# InsideLift.net
KiCad netlist of a schematic drawn in EAGLE
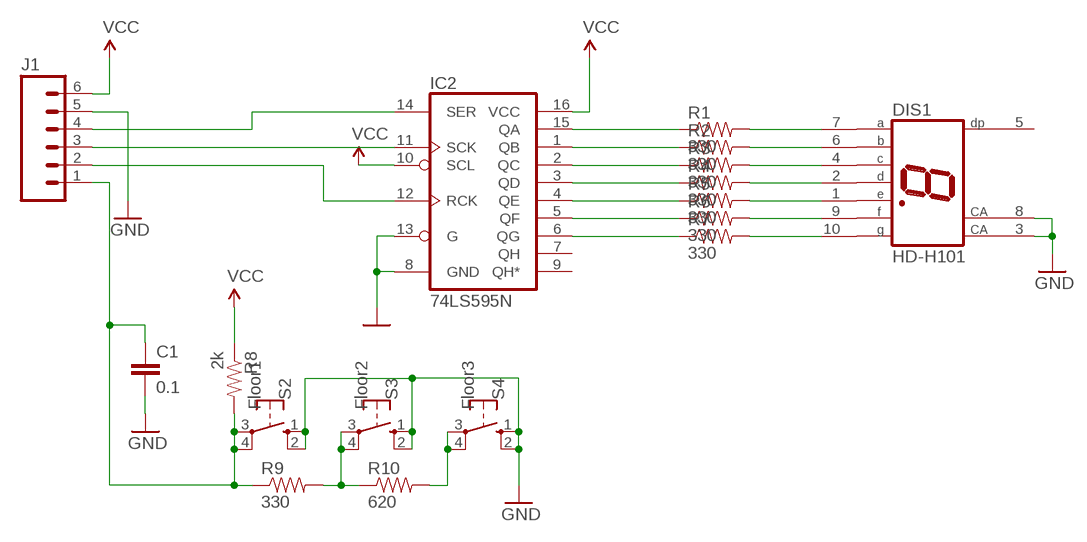
[diagram p0: schematic, sheet 1]

(export (version "E")
  (design (tool "Eeschema 10.0.6"))
  (components
    (comp (ref "C1")
      (value "0.1")
      (footprint "eagle-import:CAP-PTH-5MM")
      (libsource (lib "eagle-import") (part "CAPPTH1"))
    )
    (comp (ref "DIS1")
      (value "HD-H101")
      (footprint "eagle-import:HDSP-M")
      (libsource (lib "eagle-import") (part "HD-H101"))
    )
    (comp (ref "IC2")
      (value "74LS595N")
      (footprint "eagle-import:DIL16")
      (libsource (lib "eagle-import") (part "74595NLS"))
    )
    (comp (ref "J1")
      (value "M06LONGPADS")
      (footprint "eagle-import:1X06_LONGPADS")
      (libsource (lib "eagle-import") (part "M06LONGPADS"))
    )
    (comp (ref "R1")
      (value "330")
      (footprint "eagle-import:AXIAL-0.3")
      (libsource (lib "eagle-import") (part "SparkFun-Resistors_RESISTORAXIAL-0.3"))
    )
    (comp (ref "R2")
      (value "330")
      (footprint "eagle-import:AXIAL-0.3")
      (libsource (lib "eagle-import") (part "SparkFun-Resistors_RESISTORAXIAL-0.3"))
    )
    (comp (ref "R3")
      (value "330")
      (footprint "eagle-import:AXIAL-0.3")
      (libsource (lib "eagle-import") (part "SparkFun-Resistors_RESISTORAXIAL-0.3"))
    )
    (comp (ref "R4")
      (value "330")
      (footprint "eagle-import:AXIAL-0.3")
      (libsource (lib "eagle-import") (part "SparkFun-Resistors_RESISTORAXIAL-0.3"))
    )
    (comp (ref "R5")
      (value "330")
      (footprint "eagle-import:AXIAL-0.3")
      (libsource (lib "eagle-import") (part "SparkFun-Resistors_RESISTORAXIAL-0.3"))
    )
    (comp (ref "R6")
      (value "330")
      (footprint "eagle-import:AXIAL-0.3")
      (libsource (lib "eagle-import") (part "SparkFun-Resistors_RESISTORAXIAL-0.3"))
    )
    (comp (ref "R7")
      (value "330")
      (footprint "eagle-import:AXIAL-0.3")
      (libsource (lib "eagle-import") (part "SparkFun-Resistors_RESISTORAXIAL-0.3"))
    )
    (comp (ref "R8")
      (value "2k")
      (footprint "eagle-import:0805")
      (libsource (lib "eagle-import") (part "RESISTOR0805-RES"))
    )
    (comp (ref "R9")
      (value "330")
      (footprint "eagle-import:0805")
      (libsource (lib "eagle-import") (part "RESISTOR0805-RES"))
    )
    (comp (ref "R10")
      (value "620")
      (footprint "eagle-import:0805")
      (libsource (lib "eagle-import") (part "RESISTOR0805-RES"))
    )
    (comp (ref "S2")
      (value "Floor1")
      (footprint "eagle-import:B3F-10XX")
      (fields
        (field (name "MPN") "B3F-1000")
        (field (name "MPN_1") "B3F-1000")
        (field (name "OC_FARNELL") "176432")
        (field (name "OC_NEWARK") "36M3542")
      )
      (libsource (lib "eagle-import") (part "10-XX"))
    )
    (comp (ref "S3")
      (value "Floor2")
      (footprint "eagle-import:B3F-10XX")
      (fields
        (field (name "MPN") "B3F-1000")
        (field (name "MPN_1") "B3F-1000")
        (field (name "OC_FARNELL") "176432")
        (field (name "OC_NEWARK") "36M3542")
      )
      (libsource (lib "eagle-import") (part "10-XX"))
    )
    (comp (ref "S4")
      (value "Floor3")
      (footprint "eagle-import:B3F-10XX")
      (fields
        (field (name "MPN") "B3F-1000")
        (field (name "MPN_1") "B3F-1000")
        (field (name "OC_FARNELL") "176432")
        (field (name "OC_NEWARK") "36M3542")
      )
      (libsource (lib "eagle-import") (part "10-XX"))
    )
  )
  (nets
    (net (code "1") (name "GND") (class "Default")
      (node (ref "C1") (pin "2") (pinfunction "2_2") (pintype "passive"))
      (node (ref "DIS1") (pin "3") (pinfunction "CA_3") (pintype "passive"))
      (node (ref "DIS1") (pin "8") (pinfunction "CA_8") (pintype "passive"))
      (node (ref "IC2") (pin "13") (pinfunction "G_13") (pintype "input"))
      (node (ref "IC2") (pin "8") (pinfunction "GND_8") (pintype "power_in"))
      (node (ref "J1") (pin "5") (pinfunction "5_5") (pintype "passive"))
      (node (ref "S2") (pin "1") (pinfunction "S_1") (pintype "passive"))
      (node (ref "S2") (pin "2") (pinfunction "S1_2") (pintype "passive"))
      (node (ref "S3") (pin "1") (pinfunction "S_1") (pintype "passive"))
      (node (ref "S3") (pin "2") (pinfunction "S1_2") (pintype "passive"))
      (node (ref "S4") (pin "1") (pinfunction "S_1") (pintype "passive"))
      (node (ref "S4") (pin "2") (pinfunction "S1_2") (pintype "passive"))
    )
    (net (code "2") (name "Net-(DIS1-A)") (class "Default")
      (node (ref "DIS1") (pin "7") (pinfunction "A_7") (pintype "passive"))
      (node (ref "R1") (pin "P$2") (pinfunction "2_P$2") (pintype "passive"))
    )
    (net (code "3") (name "Net-(DIS1-B)") (class "Default")
      (node (ref "DIS1") (pin "6") (pinfunction "B_6") (pintype "passive"))
      (node (ref "R2") (pin "P$2") (pinfunction "2_P$2") (pintype "passive"))
    )
    (net (code "4") (name "Net-(DIS1-C)") (class "Default")
      (node (ref "DIS1") (pin "4") (pinfunction "C_4") (pintype "passive"))
      (node (ref "R3") (pin "P$2") (pinfunction "2_P$2") (pintype "passive"))
    )
    (net (code "5") (name "Net-(DIS1-D)") (class "Default")
      (node (ref "DIS1") (pin "2") (pinfunction "D_2") (pintype "passive"))
      (node (ref "R4") (pin "P$2") (pinfunction "2_P$2") (pintype "passive"))
    )
    (net (code "6") (name "Net-(DIS1-E)") (class "Default")
      (node (ref "DIS1") (pin "1") (pinfunction "E_1") (pintype "passive"))
      (node (ref "R5") (pin "P$2") (pinfunction "2_P$2") (pintype "passive"))
    )
    (net (code "7") (name "Net-(DIS1-F)") (class "Default")
      (node (ref "DIS1") (pin "9") (pinfunction "F_9") (pintype "passive"))
      (node (ref "R6") (pin "P$2") (pinfunction "2_P$2") (pintype "passive"))
    )
    (net (code "8") (name "Net-(DIS1-G)") (class "Default")
      (node (ref "DIS1") (pin "10") (pinfunction "G_10") (pintype "passive"))
      (node (ref "R7") (pin "P$2") (pinfunction "2_P$2") (pintype "passive"))
    )
    (net (code "9") (name "Net-(IC2-QA)") (class "Default")
      (node (ref "IC2") (pin "15") (pinfunction "QA_15") (pintype "tri_state"))
      (node (ref "R1") (pin "P$1") (pinfunction "1_P$1") (pintype "passive"))
    )
    (net (code "10") (name "Net-(IC2-QB)") (class "Default")
      (node (ref "IC2") (pin "1") (pinfunction "QB_1") (pintype "tri_state"))
      (node (ref "R2") (pin "P$1") (pinfunction "1_P$1") (pintype "passive"))
    )
    (net (code "11") (name "Net-(IC2-QC)") (class "Default")
      (node (ref "IC2") (pin "2") (pinfunction "QC_2") (pintype "tri_state"))
      (node (ref "R3") (pin "P$1") (pinfunction "1_P$1") (pintype "passive"))
    )
    (net (code "12") (name "Net-(IC2-QD)") (class "Default")
      (node (ref "IC2") (pin "3") (pinfunction "QD_3") (pintype "tri_state"))
      (node (ref "R4") (pin "P$1") (pinfunction "1_P$1") (pintype "passive"))
    )
    (net (code "13") (name "Net-(IC2-QE)") (class "Default")
      (node (ref "IC2") (pin "4") (pinfunction "QE_4") (pintype "tri_state"))
      (node (ref "R5") (pin "P$1") (pinfunction "1_P$1") (pintype "passive"))
    )
    (net (code "14") (name "Net-(IC2-QF)") (class "Default")
      (node (ref "IC2") (pin "5") (pinfunction "QF_5") (pintype "tri_state"))
      (node (ref "R6") (pin "P$1") (pinfunction "1_P$1") (pintype "passive"))
    )
    (net (code "15") (name "Net-(IC2-QG)") (class "Default")
      (node (ref "IC2") (pin "6") (pinfunction "QG_6") (pintype "tri_state"))
      (node (ref "R7") (pin "P$1") (pinfunction "1_P$1") (pintype "passive"))
    )
    (net (code "16") (name "Net-(IC2-RCK)") (class "Default")
      (node (ref "IC2") (pin "12") (pinfunction "RCK_12") (pintype "input"))
      (node (ref "J1") (pin "2") (pinfunction "2_2") (pintype "passive"))
    )
    (net (code "17") (name "Net-(IC2-SCK)") (class "Default")
      (node (ref "IC2") (pin "11") (pinfunction "SCK_11") (pintype "input"))
      (node (ref "J1") (pin "3") (pinfunction "3_3") (pintype "passive"))
    )
    (net (code "18") (name "Net-(IC2-SER)") (class "Default")
      (node (ref "IC2") (pin "14") (pinfunction "SER_14") (pintype "input"))
      (node (ref "J1") (pin "4") (pinfunction "4_4") (pintype "passive"))
    )
    (net (code "19") (name "Net-(S2-P)") (class "Default")
      (node (ref "C1") (pin "1") (pinfunction "1_1") (pintype "passive"))
      (node (ref "J1") (pin "1") (pinfunction "1_1") (pintype "passive"))
      (node (ref "R8") (pin "2") (pinfunction "2_2") (pintype "passive"))
      (node (ref "R9") (pin "1") (pinfunction "1_1") (pintype "passive"))
      (node (ref "S2") (pin "3") (pinfunction "P_3") (pintype "passive"))
      (node (ref "S2") (pin "4") (pinfunction "P1_4") (pintype "passive"))
    )
    (net (code "20") (name "Net-(S3-P)") (class "Default")
      (node (ref "R10") (pin "1") (pinfunction "1_1") (pintype "passive"))
      (node (ref "R9") (pin "2") (pinfunction "2_2") (pintype "passive"))
      (node (ref "S3") (pin "3") (pinfunction "P_3") (pintype "passive"))
      (node (ref "S3") (pin "4") (pinfunction "P1_4") (pintype "passive"))
    )
    (net (code "21") (name "Net-(S4-P)") (class "Default")
      (node (ref "R10") (pin "2") (pinfunction "2_2") (pintype "passive"))
      (node (ref "S4") (pin "3") (pinfunction "P_3") (pintype "passive"))
      (node (ref "S4") (pin "4") (pinfunction "P1_4") (pintype "passive"))
    )
    (net (code "22") (name "VCC") (class "Default")
      (node (ref "IC2") (pin "10") (pinfunction "SCL_10") (pintype "input"))
      (node (ref "IC2") (pin "16") (pinfunction "VCC_16") (pintype "power_in"))
      (node (ref "J1") (pin "6") (pinfunction "6_6") (pintype "passive"))
      (node (ref "R8") (pin "1") (pinfunction "1_1") (pintype "passive"))
    )
    (net (code "23") (name "unconnected-(DIS1-DP-Pad5)") (class "Default")
      (node (ref "DIS1") (pin "5") (pinfunction "DP_5") (pintype "passive"))
    )
    (net (code "24") (name "unconnected-(IC2-QH*-Pad9)") (class "Default")
      (node (ref "IC2") (pin "9") (pinfunction "QH*_9") (pintype "tri_state"))
    )
    (net (code "25") (name "unconnected-(IC2-QH-Pad7)") (class "Default")
      (node (ref "IC2") (pin "7") (pinfunction "QH_7") (pintype "tri_state"))
    )
  )
)
